# clockwork-backpack-1a5.net
KiCad netlist of a schematic drawn in EAGLE
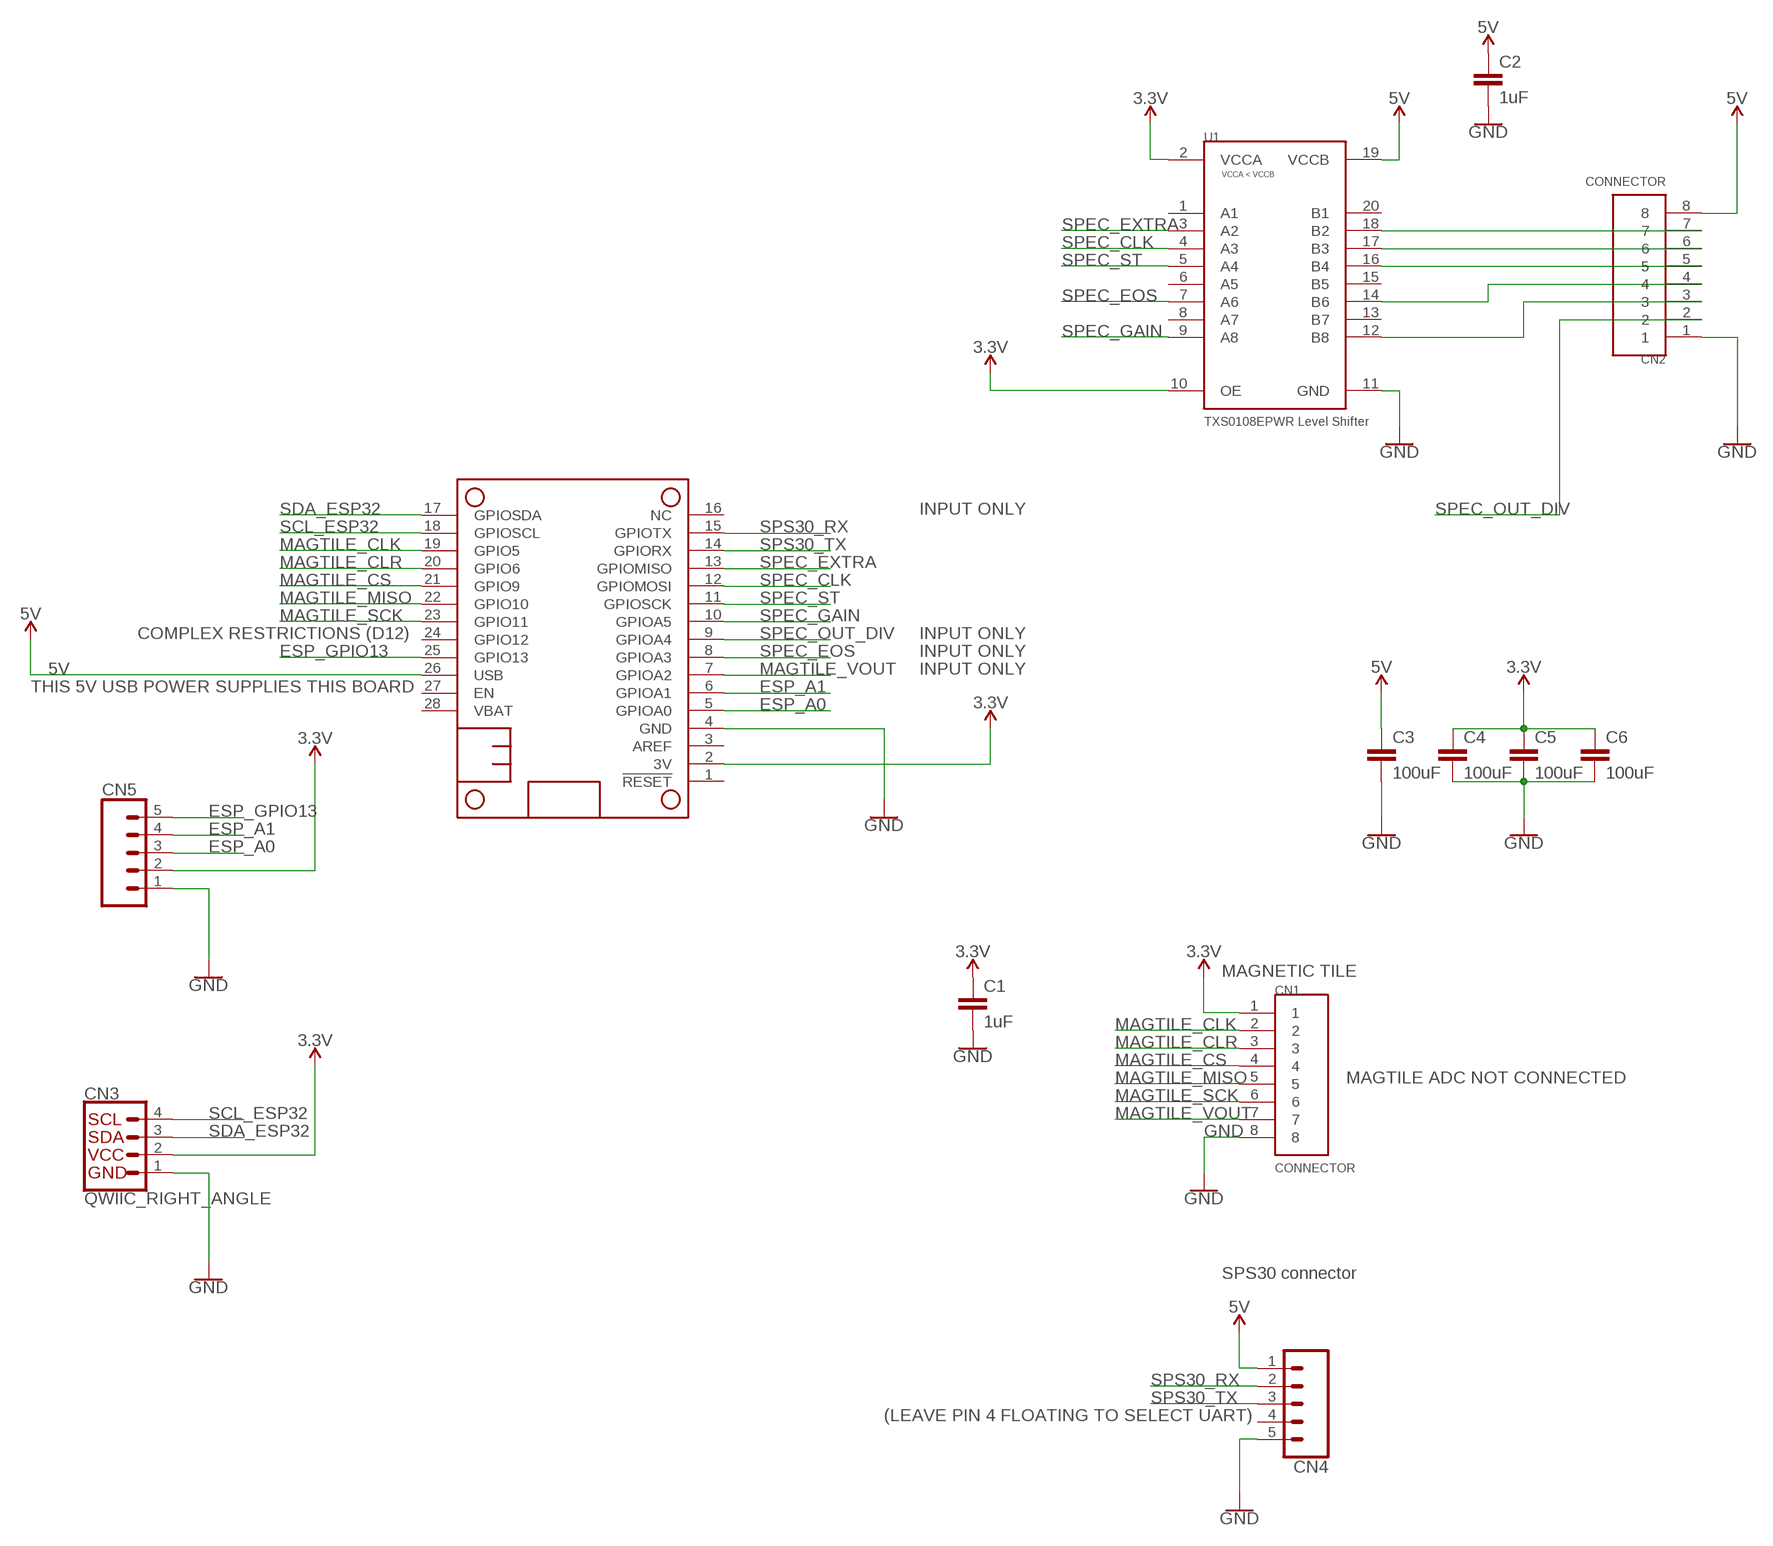
[diagram p0: schematic, sheet 1]

(export (version "E")
  (design (tool "Eeschema 10.0.6"))
  (components
    (comp (ref "C1")
      (value "1uF")
      (footprint "eagle-import:0603")
      (libsource (lib "eagle-import") (part "CAP-0603"))
    )
    (comp (ref "C2")
      (value "1uF")
      (footprint "eagle-import:0603")
      (libsource (lib "eagle-import") (part "CAP-0603"))
    )
    (comp (ref "C3")
      (value "100uF")
      (footprint "eagle-import:1206")
      (libsource (lib "eagle-import") (part "CAP-1206"))
    )
    (comp (ref "C4")
      (value "100uF")
      (footprint "eagle-import:1206")
      (libsource (lib "eagle-import") (part "CAP-1206"))
    )
    (comp (ref "C5")
      (value "100uF")
      (footprint "eagle-import:1206")
      (libsource (lib "eagle-import") (part "CAP-1206"))
    )
    (comp (ref "C6")
      (value "100uF")
      (footprint "eagle-import:1206")
      (libsource (lib "eagle-import") (part "CAP-1206"))
    )
    (comp (ref "CN1")
      (value "CON-SM08B-SRSS-TB")
      (footprint "eagle-import:CON-SM08B-SRSS-TB")
      (libsource (lib "eagle-import") (part "CON-SM08B-SRSS-TB"))
    )
    (comp (ref "CN2")
      (value "CON-SM08B-SRSS-TB")
      (footprint "eagle-import:CON-SM08B-SRSS-TB")
      (libsource (lib "eagle-import") (part "CON-SM08B-SRSS-TB"))
    )
    (comp (ref "CN3")
      (value "QWIIC_RIGHT_ANGLE")
      (footprint "eagle-import:JST04_1MM_RA")
      (libsource (lib "eagle-import") (part "QWIIC_CONNECTORJS-1MM"))
    )
    (comp (ref "CN4")
      (value "CONN_05LOCK")
      (footprint "eagle-import:1X05_LOCK")
      (libsource (lib "eagle-import") (part "CONN_05LOCK"))
    )
    (comp (ref "CN5")
      (value "CONN_05LOCK")
      (footprint "eagle-import:1X05_LOCK")
      (libsource (lib "eagle-import") (part "CONN_05LOCK"))
    )
    (comp (ref "U1")
      (value "TXS0108EPWR")
      (footprint "eagle-import:TSSOP-20")
      (libsource (lib "eagle-import") (part "TXS0108EPWR"))
    )
    (comp (ref "U2")
      (value "FEATHERWING_NODIM")
      (footprint "eagle-import:FEATHERWING_DIM")
      (libsource (lib "eagle-import") (part "FEATHERWING_NODIM"))
    )
  )
  (nets
    (net (code "1") (name "/ESP_A0") (class "Default")
      (node (ref "CN5") (pin "3") (pinfunction "3_3") (pintype "passive"))
      (node (ref "U2") (pin "5") (pinfunction "GPIOA0_5") (pintype "bidirectional"))
    )
    (net (code "2") (name "/ESP_A1") (class "Default")
      (node (ref "CN5") (pin "4") (pinfunction "4_4") (pintype "passive"))
      (node (ref "U2") (pin "6") (pinfunction "GPIOA1_6") (pintype "bidirectional"))
    )
    (net (code "3") (name "/ESP_GPIO13") (class "Default")
      (node (ref "CN5") (pin "5") (pinfunction "5_5") (pintype "passive"))
      (node (ref "U2") (pin "25") (pinfunction "GPIO13_25") (pintype "bidirectional"))
    )
    (net (code "4") (name "/MAGTILE_CLK") (class "Default")
      (node (ref "CN1") (pin "2") (pinfunction "2_2") (pintype "bidirectional"))
      (node (ref "U2") (pin "19") (pinfunction "GPIO5_19") (pintype "bidirectional"))
    )
    (net (code "5") (name "/MAGTILE_CLR") (class "Default")
      (node (ref "CN1") (pin "3") (pinfunction "3_3") (pintype "bidirectional"))
      (node (ref "U2") (pin "20") (pinfunction "GPIO6_20") (pintype "bidirectional"))
    )
    (net (code "6") (name "/MAGTILE_CS") (class "Default")
      (node (ref "CN1") (pin "4") (pinfunction "4_4") (pintype "bidirectional"))
      (node (ref "U2") (pin "21") (pinfunction "GPIO9_21") (pintype "bidirectional"))
    )
    (net (code "7") (name "/MAGTILE_MISO") (class "Default")
      (node (ref "CN1") (pin "5") (pinfunction "5_5") (pintype "bidirectional"))
      (node (ref "U2") (pin "22") (pinfunction "GPIO10_22") (pintype "bidirectional"))
    )
    (net (code "8") (name "/MAGTILE_SCK") (class "Default")
      (node (ref "CN1") (pin "6") (pinfunction "6_6") (pintype "bidirectional"))
      (node (ref "U2") (pin "23") (pinfunction "GPIO11_23") (pintype "bidirectional"))
    )
    (net (code "9") (name "/MAGTILE_VOUT") (class "Default")
      (node (ref "CN1") (pin "7") (pinfunction "7_7") (pintype "bidirectional"))
      (node (ref "U2") (pin "7") (pinfunction "GPIOA2_7") (pintype "bidirectional"))
    )
    (net (code "10") (name "/SCL_ESP32") (class "Default")
      (node (ref "CN3") (pin "4") (pinfunction "4_4") (pintype "passive"))
      (node (ref "U2") (pin "18") (pinfunction "GPIOSCL_18") (pintype "bidirectional"))
    )
    (net (code "11") (name "/SDA_ESP32") (class "Default")
      (node (ref "CN3") (pin "3") (pinfunction "3_3") (pintype "passive"))
      (node (ref "U2") (pin "17") (pinfunction "GPIOSDA_17") (pintype "bidirectional"))
    )
    (net (code "12") (name "/SPEC_CLK") (class "Default")
      (node (ref "U1") (pin "4") (pinfunction "A3_4") (pintype "bidirectional"))
      (node (ref "U2") (pin "12") (pinfunction "GPIOMOSI_12") (pintype "bidirectional"))
    )
    (net (code "13") (name "/SPEC_EOS") (class "Default")
      (node (ref "U1") (pin "7") (pinfunction "A6_7") (pintype "bidirectional"))
      (node (ref "U2") (pin "8") (pinfunction "GPIOA3_8") (pintype "bidirectional"))
    )
    (net (code "14") (name "/SPEC_EXTRA") (class "Default")
      (node (ref "U1") (pin "3") (pinfunction "A2_3") (pintype "bidirectional"))
      (node (ref "U2") (pin "13") (pinfunction "GPIOMISO_13") (pintype "bidirectional"))
    )
    (net (code "15") (name "/SPEC_GAIN") (class "Default")
      (node (ref "U1") (pin "9") (pinfunction "A8_9") (pintype "bidirectional"))
      (node (ref "U2") (pin "10") (pinfunction "GPIOA5_10") (pintype "bidirectional"))
    )
    (net (code "16") (name "/SPEC_OUT_DIV") (class "Default")
      (node (ref "CN2") (pin "2") (pinfunction "2_2") (pintype "bidirectional"))
      (node (ref "U2") (pin "9") (pinfunction "GPIOA4_9") (pintype "bidirectional"))
    )
    (net (code "17") (name "/SPEC_ST") (class "Default")
      (node (ref "U1") (pin "5") (pinfunction "A4_5") (pintype "bidirectional"))
      (node (ref "U2") (pin "11") (pinfunction "GPIOSCK_11") (pintype "bidirectional"))
    )
    (net (code "18") (name "/SPS30_RX") (class "Default")
      (node (ref "CN4") (pin "2") (pinfunction "2_2") (pintype "passive"))
      (node (ref "U2") (pin "15") (pinfunction "GPIOTX_15") (pintype "bidirectional"))
    )
    (net (code "19") (name "/SPS30_TX") (class "Default")
      (node (ref "CN4") (pin "3") (pinfunction "3_3") (pintype "passive"))
      (node (ref "U2") (pin "14") (pinfunction "GPIORX_14") (pintype "bidirectional"))
    )
    (net (code "20") (name "/VBAT") (class "Default")
      (node (ref "U2") (pin "28") (pinfunction "VBAT_28") (pintype "power_in"))
    )
    (net (code "21") (name "3.3V") (class "Default")
      (node (ref "C1") (pin "1") (pinfunction "1_1") (pintype "passive"))
      (node (ref "C4") (pin "1") (pinfunction "1_1") (pintype "passive"))
      (node (ref "C5") (pin "1") (pinfunction "1_1") (pintype "passive"))
      (node (ref "C6") (pin "1") (pinfunction "1_1") (pintype "passive"))
      (node (ref "CN1") (pin "1") (pinfunction "1_1") (pintype "bidirectional"))
      (node (ref "CN3") (pin "2") (pinfunction "2_2") (pintype "power_in"))
      (node (ref "CN5") (pin "2") (pinfunction "2_2") (pintype "passive"))
      (node (ref "U1") (pin "10") (pinfunction "OE_10") (pintype "bidirectional"))
      (node (ref "U1") (pin "2") (pinfunction "VCCA_2") (pintype "bidirectional"))
      (node (ref "U2") (pin "2") (pinfunction "3V_2") (pintype "power_in"))
    )
    (net (code "22") (name "5V") (class "Default")
      (node (ref "C2") (pin "1") (pinfunction "1_1") (pintype "passive"))
      (node (ref "C3") (pin "1") (pinfunction "1_1") (pintype "passive"))
      (node (ref "CN2") (pin "8") (pinfunction "8_8") (pintype "bidirectional"))
      (node (ref "CN4") (pin "1") (pinfunction "1_1") (pintype "passive"))
      (node (ref "U1") (pin "19") (pinfunction "VCCB_19") (pintype "bidirectional"))
      (node (ref "U2") (pin "26") (pinfunction "USB_26") (pintype "power_in"))
    )
    (net (code "23") (name "GND") (class "Default")
      (node (ref "C1") (pin "2") (pinfunction "2_2") (pintype "passive"))
      (node (ref "C2") (pin "2") (pinfunction "2_2") (pintype "passive"))
      (node (ref "C3") (pin "2") (pinfunction "2_2") (pintype "passive"))
      (node (ref "C4") (pin "2") (pinfunction "2_2") (pintype "passive"))
      (node (ref "C5") (pin "2") (pinfunction "2_2") (pintype "passive"))
      (node (ref "C6") (pin "2") (pinfunction "2_2") (pintype "passive"))
      (node (ref "CN1") (pin "8") (pinfunction "8_8") (pintype "bidirectional"))
      (node (ref "CN2") (pin "1") (pinfunction "1_1") (pintype "bidirectional"))
      (node (ref "CN3") (pin "1") (pinfunction "1_1") (pintype "power_in"))
      (node (ref "CN4") (pin "5") (pinfunction "5_5") (pintype "passive"))
      (node (ref "CN5") (pin "1") (pinfunction "1_1") (pintype "passive"))
      (node (ref "U1") (pin "11") (pinfunction "GND_11") (pintype "bidirectional"))
      (node (ref "U2") (pin "4") (pinfunction "GND_4") (pintype "power_in"))
    )
    (net (code "24") (name "Net-(U1-B2)") (class "Default")
      (node (ref "CN2") (pin "7") (pinfunction "7_7") (pintype "bidirectional"))
      (node (ref "U1") (pin "18") (pinfunction "B2_18") (pintype "bidirectional"))
    )
    (net (code "25") (name "Net-(U1-B3)") (class "Default")
      (node (ref "CN2") (pin "6") (pinfunction "6_6") (pintype "bidirectional"))
      (node (ref "U1") (pin "17") (pinfunction "B3_17") (pintype "bidirectional"))
    )
    (net (code "26") (name "Net-(U1-B4)") (class "Default")
      (node (ref "CN2") (pin "5") (pinfunction "5_5") (pintype "bidirectional"))
      (node (ref "U1") (pin "16") (pinfunction "B4_16") (pintype "bidirectional"))
    )
    (net (code "27") (name "Net-(U1-B6)") (class "Default")
      (node (ref "CN2") (pin "4") (pinfunction "4_4") (pintype "bidirectional"))
      (node (ref "U1") (pin "14") (pinfunction "B6_14") (pintype "bidirectional"))
    )
    (net (code "28") (name "Net-(U1-B8)") (class "Default")
      (node (ref "CN2") (pin "3") (pinfunction "3_3") (pintype "bidirectional"))
      (node (ref "U1") (pin "12") (pinfunction "B8_12") (pintype "bidirectional"))
    )
    (net (code "29") (name "unconnected-(CN4-Pad4)") (class "Default")
      (node (ref "CN4") (pin "4") (pinfunction "4_4") (pintype "passive"))
    )
    (net (code "30") (name "unconnected-(U1-A1-Pad1)") (class "Default")
      (node (ref "U1") (pin "1") (pinfunction "A1_1") (pintype "bidirectional"))
    )
    (net (code "31") (name "unconnected-(U1-A5-Pad6)") (class "Default")
      (node (ref "U1") (pin "6") (pinfunction "A5_6") (pintype "bidirectional"))
    )
    (net (code "32") (name "unconnected-(U1-A7-Pad8)") (class "Default")
      (node (ref "U1") (pin "8") (pinfunction "A7_8") (pintype "bidirectional"))
    )
    (net (code "33") (name "unconnected-(U1-B1-Pad20)") (class "Default")
      (node (ref "U1") (pin "20") (pinfunction "B1_20") (pintype "bidirectional"))
    )
    (net (code "34") (name "unconnected-(U1-B5-Pad15)") (class "Default")
      (node (ref "U1") (pin "15") (pinfunction "B5_15") (pintype "bidirectional"))
    )
    (net (code "35") (name "unconnected-(U1-B7-Pad13)") (class "Default")
      (node (ref "U1") (pin "13") (pinfunction "B7_13") (pintype "bidirectional"))
    )
    (net (code "36") (name "unconnected-(U2-AREF-Pad3)") (class "Default")
      (node (ref "U2") (pin "3") (pinfunction "AREF_3") (pintype "passive"))
    )
    (net (code "37") (name "unconnected-(U2-EN-Pad27)") (class "Default")
      (node (ref "U2") (pin "27") (pinfunction "EN_27") (pintype "passive"))
    )
    (net (code "38") (name "unconnected-(U2-GPIO12-Pad24)") (class "Default")
      (node (ref "U2") (pin "24") (pinfunction "GPIO12_24") (pintype "bidirectional"))
    )
    (net (code "39") (name "unconnected-(U2-NC-Pad16)") (class "Default")
      (node (ref "U2") (pin "16") (pinfunction "NC_16") (pintype "passive"))
    )
    (net (code "40") (name "unconnected-(U2-~{RESET}-Pad1)") (class "Default")
      (node (ref "U2") (pin "1") (pinfunction "~{RESET}_1") (pintype "input"))
    )
  )
)
